# Small.net
KiCad netlist of a schematic drawn in EAGLE
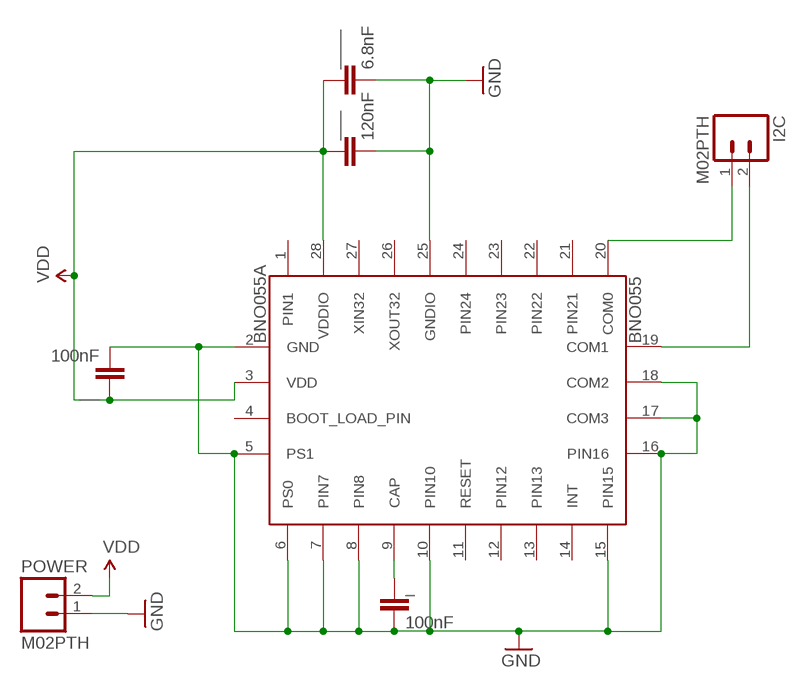
[diagram p0: schematic, sheet 1]

(export (version "E")
  (design (tool "Eeschema 10.0.6"))
  (components
    (comp (ref "BNO055")
      (value "BNO055A")
      (footprint "eagle-import:BNO055")
      (libsource (lib "eagle-import") (part "BNO055A"))
    )
    (comp (ref "I2C")
      (value "M02PTH")
      (footprint "eagle-import:1X02")
      (libsource (lib "eagle-import") (part "M02PTH"))
    )
    (comp (ref "POWER")
      (value "M02PTH")
      (footprint "eagle-import:1X02")
      (libsource (lib "eagle-import") (part "M02PTH"))
    )
    (comp (ref "_")
      (value "100nF")
      (footprint "eagle-import:1206")
      (libsource (lib "eagle-import") (part "CAP1206"))
    )
    (comp (ref "__")
      (value "100nF")
      (footprint "eagle-import:1206")
      (libsource (lib "eagle-import") (part "CAP1206"))
    )
    (comp (ref "___")
      (value "120nF")
      (footprint "eagle-import:1206")
      (libsource (lib "eagle-import") (part "CAP1206"))
    )
    (comp (ref "____")
      (value "6.8nF")
      (footprint "eagle-import:1206")
      (libsource (lib "eagle-import") (part "CAP1206"))
    )
  )
  (nets
    (net (code "1") (name "GND") (class "Default")
      (node (ref "BNO055") (pin "10") (pinfunction "PIN10_10") (pintype "bidirectional"))
      (node (ref "BNO055") (pin "15") (pinfunction "PIN15_15") (pintype "bidirectional"))
      (node (ref "BNO055") (pin "16") (pinfunction "PIN16_16") (pintype "bidirectional"))
      (node (ref "BNO055") (pin "17") (pinfunction "COM3_17") (pintype "bidirectional"))
      (node (ref "BNO055") (pin "18") (pinfunction "COM2_18") (pintype "bidirectional"))
      (node (ref "BNO055") (pin "2") (pinfunction "GND_2") (pintype "bidirectional"))
      (node (ref "BNO055") (pin "25") (pinfunction "GNDIO_25") (pintype "bidirectional"))
      (node (ref "BNO055") (pin "5") (pinfunction "PS1_5") (pintype "bidirectional"))
      (node (ref "BNO055") (pin "6") (pinfunction "PS0_6") (pintype "bidirectional"))
      (node (ref "BNO055") (pin "7") (pinfunction "PIN7_7") (pintype "bidirectional"))
      (node (ref "BNO055") (pin "8") (pinfunction "PIN8_8") (pintype "bidirectional"))
      (node (ref "POWER") (pin "1") (pinfunction "1_1") (pintype "passive"))
      (node (ref "_") (pin "2") (pinfunction "2_2") (pintype "passive"))
      (node (ref "__") (pin "2") (pinfunction "2_2") (pintype "passive"))
      (node (ref "___") (pin "2") (pinfunction "2_2") (pintype "passive"))
      (node (ref "____") (pin "2") (pinfunction "2_2") (pintype "passive"))
    )
    (net (code "2") (name "Net-(BNO055-CAP)") (class "Default")
      (node (ref "BNO055") (pin "9") (pinfunction "CAP_9") (pintype "bidirectional"))
      (node (ref "_") (pin "1") (pinfunction "1_1") (pintype "passive"))
    )
    (net (code "3") (name "Net-(BNO055-COM0)") (class "Default")
      (node (ref "BNO055") (pin "20") (pinfunction "COM0_20") (pintype "bidirectional"))
      (node (ref "I2C") (pin "1") (pinfunction "1_1") (pintype "passive"))
    )
    (net (code "4") (name "Net-(BNO055-COM1)") (class "Default")
      (node (ref "BNO055") (pin "19") (pinfunction "COM1_19") (pintype "bidirectional"))
      (node (ref "I2C") (pin "2") (pinfunction "2_2") (pintype "passive"))
    )
    (net (code "5") (name "VDD") (class "Default")
      (node (ref "BNO055") (pin "28") (pinfunction "VDDIO_28") (pintype "bidirectional"))
      (node (ref "BNO055") (pin "3") (pinfunction "VDD_3") (pintype "bidirectional"))
      (node (ref "POWER") (pin "2") (pinfunction "2_2") (pintype "passive"))
      (node (ref "__") (pin "1") (pinfunction "1_1") (pintype "passive"))
      (node (ref "___") (pin "1") (pinfunction "1_1") (pintype "passive"))
      (node (ref "____") (pin "1") (pinfunction "1_1") (pintype "passive"))
    )
    (net (code "6") (name "unconnected-(BNO055-BOOT_LOAD_PIN-Pad4)") (class "Default")
      (node (ref "BNO055") (pin "4") (pinfunction "BOOT_LOAD_PIN_4") (pintype "bidirectional"))
    )
    (net (code "7") (name "unconnected-(BNO055-INT-Pad14)") (class "Default")
      (node (ref "BNO055") (pin "14") (pinfunction "INT_14") (pintype "bidirectional"))
    )
    (net (code "8") (name "unconnected-(BNO055-PIN1-Pad1)") (class "Default")
      (node (ref "BNO055") (pin "1") (pinfunction "PIN1_1") (pintype "bidirectional"))
    )
    (net (code "9") (name "unconnected-(BNO055-PIN12-Pad12)") (class "Default")
      (node (ref "BNO055") (pin "12") (pinfunction "PIN12_12") (pintype "bidirectional"))
    )
    (net (code "10") (name "unconnected-(BNO055-PIN13-Pad13)") (class "Default")
      (node (ref "BNO055") (pin "13") (pinfunction "PIN13_13") (pintype "bidirectional"))
    )
    (net (code "11") (name "unconnected-(BNO055-PIN21-Pad21)") (class "Default")
      (node (ref "BNO055") (pin "21") (pinfunction "PIN21_21") (pintype "bidirectional"))
    )
    (net (code "12") (name "unconnected-(BNO055-PIN22-Pad22)") (class "Default")
      (node (ref "BNO055") (pin "22") (pinfunction "PIN22_22") (pintype "bidirectional"))
    )
    (net (code "13") (name "unconnected-(BNO055-PIN23-Pad23)") (class "Default")
      (node (ref "BNO055") (pin "23") (pinfunction "PIN23_23") (pintype "bidirectional"))
    )
    (net (code "14") (name "unconnected-(BNO055-PIN24-Pad24)") (class "Default")
      (node (ref "BNO055") (pin "24") (pinfunction "PIN24_24") (pintype "bidirectional"))
    )
    (net (code "15") (name "unconnected-(BNO055-RESET-Pad11)") (class "Default")
      (node (ref "BNO055") (pin "11") (pinfunction "RESET_11") (pintype "bidirectional"))
    )
    (net (code "16") (name "unconnected-(BNO055-XIN32-Pad27)") (class "Default")
      (node (ref "BNO055") (pin "27") (pinfunction "XIN32_27") (pintype "bidirectional"))
    )
    (net (code "17") (name "unconnected-(BNO055-XOUT32-Pad26)") (class "Default")
      (node (ref "BNO055") (pin "26") (pinfunction "XOUT32_26") (pintype "bidirectional"))
    )
  )
)
